# Arduino_clone.net
KiCad netlist of a schematic drawn in EAGLE
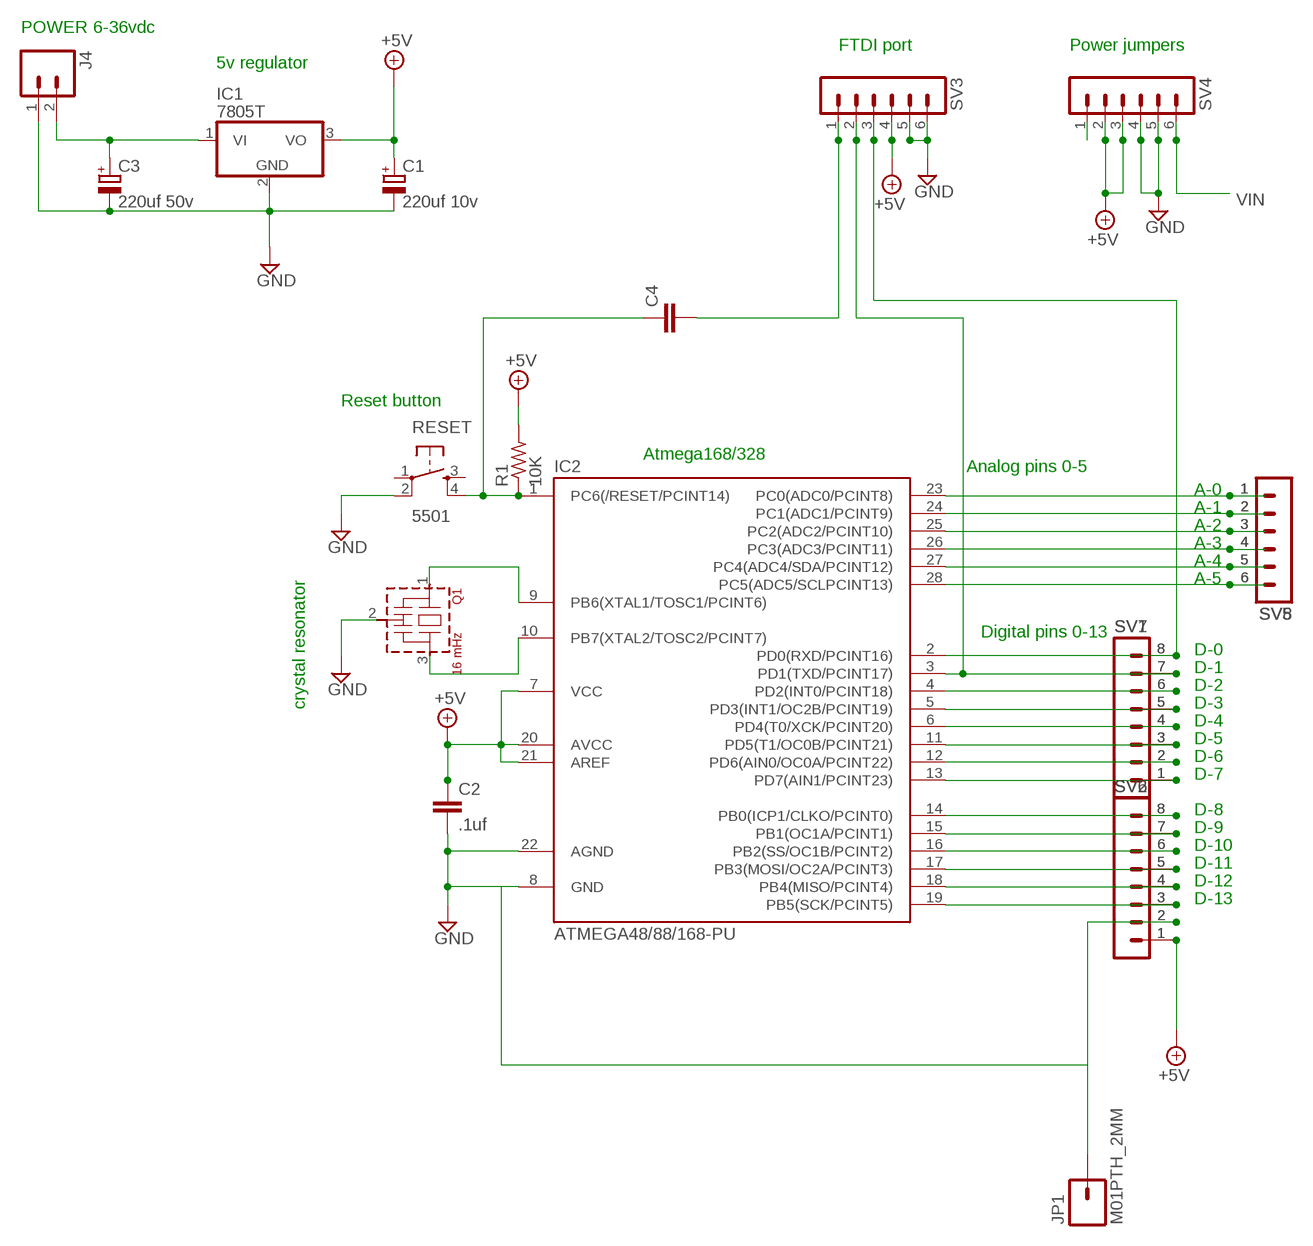
[diagram p0: schematic, sheet 1]

(export (version "E")
  (design (tool "Eeschema 10.0.6"))
  (components
    (comp (ref "C1")
      (value "220uf 10v")
      (footprint "eagle-import:E2,5-6")
      (libsource (lib "eagle-import") (part "CPOL-EUE2.5-6"))
    )
    (comp (ref "C2")
      (value ".1uf")
      (footprint "eagle-import:C050-024X044")
      (libsource (lib "eagle-import") (part "C-EU050-024X044"))
    )
    (comp (ref "C3")
      (value "220uf 50v")
      (footprint "eagle-import:E2,5-6")
      (libsource (lib "eagle-import") (part "CPOL-EUE2.5-6"))
    )
    (comp (ref "C4")
      (value "C-EU075-032X103")
      (footprint "eagle-import:C075-032X103")
      (libsource (lib "eagle-import") (part "C-EU075-032X103"))
    )
    (comp (ref "IC1")
      (value "7805T")
      (footprint "eagle-import:TO220H")
      (libsource (lib "eagle-import") (part "78T05"))
    )
    (comp (ref "IC2")
      (value "ATMEGA48/88/168-PU")
      (footprint "eagle-import:DIL28-3")
      (libsource (lib "eagle-import") (part "ATMEGA48/88/168-PU"))
    )
    (comp (ref "J4")
      (value "M02LOCK")
      (footprint "eagle-import:1X02_LOCK")
      (libsource (lib "eagle-import") (part "M02LOCK"))
    )
    (comp (ref "JP1")
      (value "M01PTH_2MM")
      (footprint "eagle-import:1X01_2MM")
      (libsource (lib "eagle-import") (part "M01PTH_2MM"))
    )
    (comp (ref "Q1")
      (value "16 mHz")
      (footprint "eagle-import:CSTLS_X")
      (libsource (lib "eagle-import") (part "CSTLS_X"))
    )
    (comp (ref "R1")
      (value "10K")
      (footprint "eagle-import:0204_5")
      (libsource (lib "eagle-import") (part "R-US_0204/5"))
    )
    (comp (ref "RESET")
      (value "5501")
      (footprint "eagle-import:TACTILE-PTH")
      (libsource (lib "eagle-import") (part "TAC_SWITCHPTH"))
    )
    (comp (ref "SV1")
      (value "MA08-1")
      (footprint "eagle-import:MA08-1")
      (libsource (lib "eagle-import") (part "MA08-1"))
    )
    (comp (ref "SV2")
      (value "MA08-1")
      (footprint "eagle-import:MA08-1")
      (libsource (lib "eagle-import") (part "MA08-1"))
    )
    (comp (ref "SV3")
      (value "MA06-1")
      (footprint "eagle-import:MA06-1")
      (libsource (lib "eagle-import") (part "MA06-1"))
    )
    (comp (ref "SV4")
      (value "MA06-1")
      (footprint "eagle-import:MA06-1")
      (libsource (lib "eagle-import") (part "MA06-1"))
    )
    (comp (ref "SV5")
      (value "MA06-1")
      (footprint "eagle-import:MA06-1")
      (libsource (lib "eagle-import") (part "MA06-1"))
    )
    (comp (ref "SV6")
      (value "MA08-1")
      (footprint "eagle-import:MA08-1")
      (libsource (lib "eagle-import") (part "MA08-1"))
    )
    (comp (ref "SV7")
      (value "MA08-1")
      (footprint "eagle-import:MA08-1")
      (libsource (lib "eagle-import") (part "MA08-1"))
    )
    (comp (ref "SV8")
      (value "MA06-1")
      (footprint "eagle-import:MA06-1")
      (libsource (lib "eagle-import") (part "MA06-1"))
    )
  )
  (nets
    (net (code "1") (name "+5V") (class "Default")
      (node (ref "C1") (pin "+") (pinfunction "+_+") (pintype "passive"))
      (node (ref "C2") (pin "1") (pinfunction "1_1") (pintype "passive"))
      (node (ref "IC1") (pin "3") (pinfunction "VO_3") (pintype "passive"))
      (node (ref "IC2") (pin "20") (pinfunction "AVCC_20") (pintype "passive"))
      (node (ref "IC2") (pin "21") (pinfunction "AREF_21") (pintype "passive"))
      (node (ref "IC2") (pin "7") (pinfunction "VCC_7") (pintype "power_in"))
      (node (ref "R1") (pin "2") (pinfunction "2_2") (pintype "passive"))
      (node (ref "SV2") (pin "1") (pinfunction "1_1") (pintype "passive"))
      (node (ref "SV3") (pin "4") (pinfunction "4_4") (pintype "passive"))
      (node (ref "SV4") (pin "2") (pinfunction "2_2") (pintype "passive"))
      (node (ref "SV4") (pin "3") (pinfunction "3_3") (pintype "passive"))
      (node (ref "SV6") (pin "1") (pinfunction "1_1") (pintype "passive"))
    )
    (net (code "2") (name "/VIN") (class "Default")
      (node (ref "C3") (pin "+") (pinfunction "+_+") (pintype "passive"))
      (node (ref "IC1") (pin "1") (pinfunction "VI_1") (pintype "input"))
      (node (ref "J4") (pin "2") (pinfunction "2_2") (pintype "passive"))
      (node (ref "SV4") (pin "6") (pinfunction "6_6") (pintype "passive"))
    )
    (net (code "3") (name "GND") (class "Default")
      (node (ref "C1") (pin "-") (pinfunction "-_-") (pintype "passive"))
      (node (ref "C2") (pin "2") (pinfunction "2_2") (pintype "passive"))
      (node (ref "C3") (pin "-") (pinfunction "-_-") (pintype "passive"))
      (node (ref "IC1") (pin "2") (pinfunction "GND_2") (pintype "passive"))
      (node (ref "IC2") (pin "22") (pinfunction "AGND_22") (pintype "power_in"))
      (node (ref "IC2") (pin "8") (pinfunction "GND_8") (pintype "power_in"))
      (node (ref "J4") (pin "1") (pinfunction "1_1") (pintype "passive"))
      (node (ref "JP1") (pin "1") (pinfunction "1_1") (pintype "passive"))
      (node (ref "Q1") (pin "2") (pinfunction "VSS_2") (pintype "power_in"))
      (node (ref "RESET") (pin "2") (pinfunction "2_2") (pintype "passive"))
      (node (ref "SV2") (pin "2") (pinfunction "2_2") (pintype "passive"))
      (node (ref "SV3") (pin "5") (pinfunction "5_5") (pintype "passive"))
      (node (ref "SV3") (pin "6") (pinfunction "6_6") (pintype "passive"))
      (node (ref "SV4") (pin "4") (pinfunction "4_4") (pintype "passive"))
      (node (ref "SV4") (pin "5") (pinfunction "5_5") (pintype "passive"))
      (node (ref "SV6") (pin "2") (pinfunction "2_2") (pintype "passive"))
    )
    (net (code "4") (name "Net-(C4-Pad2)") (class "Default")
      (node (ref "C4") (pin "2") (pinfunction "2_2") (pintype "passive"))
      (node (ref "SV3") (pin "1") (pinfunction "1_1") (pintype "passive"))
    )
    (net (code "5") (name "Net-(IC2-PB0(ICP1{slash}CLKO{slash}PCINT0))") (class "Default")
      (node (ref "IC2") (pin "14") (pinfunction "PB0(ICP1/CLKO/PCINT0)_14") (pintype "bidirectional"))
      (node (ref "SV2") (pin "8") (pinfunction "8_8") (pintype "passive"))
      (node (ref "SV6") (pin "8") (pinfunction "8_8") (pintype "passive"))
    )
    (net (code "6") (name "Net-(IC2-PB1(OC1A{slash}PCINT1))") (class "Default")
      (node (ref "IC2") (pin "15") (pinfunction "PB1(OC1A/PCINT1)_15") (pintype "bidirectional"))
      (node (ref "SV2") (pin "7") (pinfunction "7_7") (pintype "passive"))
      (node (ref "SV6") (pin "7") (pinfunction "7_7") (pintype "passive"))
    )
    (net (code "7") (name "Net-(IC2-PB2(SS{slash}OC1B{slash}PCINT2))") (class "Default")
      (node (ref "IC2") (pin "16") (pinfunction "PB2(SS/OC1B/PCINT2)_16") (pintype "bidirectional"))
      (node (ref "SV2") (pin "6") (pinfunction "6_6") (pintype "passive"))
      (node (ref "SV6") (pin "6") (pinfunction "6_6") (pintype "passive"))
    )
    (net (code "8") (name "Net-(IC2-PB3(MOSI{slash}OC2A{slash}PCINT3))") (class "Default")
      (node (ref "IC2") (pin "17") (pinfunction "PB3(MOSI/OC2A/PCINT3)_17") (pintype "bidirectional"))
      (node (ref "SV2") (pin "5") (pinfunction "5_5") (pintype "passive"))
      (node (ref "SV6") (pin "5") (pinfunction "5_5") (pintype "passive"))
    )
    (net (code "9") (name "Net-(IC2-PB4(MISO{slash}PCINT4))") (class "Default")
      (node (ref "IC2") (pin "18") (pinfunction "PB4(MISO/PCINT4)_18") (pintype "bidirectional"))
      (node (ref "SV2") (pin "4") (pinfunction "4_4") (pintype "passive"))
      (node (ref "SV6") (pin "4") (pinfunction "4_4") (pintype "passive"))
    )
    (net (code "10") (name "Net-(IC2-PB5(SCK{slash}PCINT5))") (class "Default")
      (node (ref "IC2") (pin "19") (pinfunction "PB5(SCK/PCINT5)_19") (pintype "bidirectional"))
      (node (ref "SV2") (pin "3") (pinfunction "3_3") (pintype "passive"))
      (node (ref "SV6") (pin "3") (pinfunction "3_3") (pintype "passive"))
    )
    (net (code "11") (name "Net-(IC2-PB6(XTAL1{slash}TOSC1{slash}PCINT6))") (class "Default")
      (node (ref "IC2") (pin "9") (pinfunction "PB6(XTAL1/TOSC1/PCINT6)_9") (pintype "bidirectional"))
      (node (ref "Q1") (pin "1") (pinfunction "1_1") (pintype "output"))
    )
    (net (code "12") (name "Net-(IC2-PB7(XTAL2{slash}TOSC2{slash}PCINT7))") (class "Default")
      (node (ref "IC2") (pin "10") (pinfunction "PB7(XTAL2/TOSC2/PCINT7)_10") (pintype "bidirectional"))
      (node (ref "Q1") (pin "3") (pinfunction "3_3") (pintype "input"))
    )
    (net (code "13") (name "Net-(IC2-PC0(ADC0{slash}PCINT8))") (class "Default")
      (node (ref "IC2") (pin "23") (pinfunction "PC0(ADC0/PCINT8)_23") (pintype "bidirectional"))
      (node (ref "SV5") (pin "1") (pinfunction "1_1") (pintype "passive"))
      (node (ref "SV8") (pin "1") (pinfunction "1_1") (pintype "passive"))
    )
    (net (code "14") (name "Net-(IC2-PC1(ADC1{slash}PCINT9))") (class "Default")
      (node (ref "IC2") (pin "24") (pinfunction "PC1(ADC1/PCINT9)_24") (pintype "bidirectional"))
      (node (ref "SV5") (pin "2") (pinfunction "2_2") (pintype "passive"))
      (node (ref "SV8") (pin "2") (pinfunction "2_2") (pintype "passive"))
    )
    (net (code "15") (name "Net-(IC2-PC2(ADC2{slash}PCINT10))") (class "Default")
      (node (ref "IC2") (pin "25") (pinfunction "PC2(ADC2/PCINT10)_25") (pintype "bidirectional"))
      (node (ref "SV5") (pin "3") (pinfunction "3_3") (pintype "passive"))
      (node (ref "SV8") (pin "3") (pinfunction "3_3") (pintype "passive"))
    )
    (net (code "16") (name "Net-(IC2-PC3(ADC3{slash}PCINT11))") (class "Default")
      (node (ref "IC2") (pin "26") (pinfunction "PC3(ADC3/PCINT11)_26") (pintype "bidirectional"))
      (node (ref "SV5") (pin "4") (pinfunction "4_4") (pintype "passive"))
      (node (ref "SV8") (pin "4") (pinfunction "4_4") (pintype "passive"))
    )
    (net (code "17") (name "Net-(IC2-PC4(ADC4{slash}SDA{slash}PCINT12))") (class "Default")
      (node (ref "IC2") (pin "27") (pinfunction "PC4(ADC4/SDA/PCINT12)_27") (pintype "bidirectional"))
      (node (ref "SV5") (pin "5") (pinfunction "5_5") (pintype "passive"))
      (node (ref "SV8") (pin "5") (pinfunction "5_5") (pintype "passive"))
    )
    (net (code "18") (name "Net-(IC2-PC5(ADC5{slash}SCLPCINT13))") (class "Default")
      (node (ref "IC2") (pin "28") (pinfunction "PC5(ADC5/SCLPCINT13)_28") (pintype "bidirectional"))
      (node (ref "SV5") (pin "6") (pinfunction "6_6") (pintype "passive"))
      (node (ref "SV8") (pin "6") (pinfunction "6_6") (pintype "passive"))
    )
    (net (code "19") (name "Net-(IC2-PC6({slash}RESET{slash}PCINT14))") (class "Default")
      (node (ref "C4") (pin "1") (pinfunction "1_1") (pintype "passive"))
      (node (ref "IC2") (pin "1") (pinfunction "PC6(/RESET/PCINT14)_1") (pintype "bidirectional"))
      (node (ref "R1") (pin "1") (pinfunction "1_1") (pintype "passive"))
      (node (ref "RESET") (pin "4") (pinfunction "4_4") (pintype "passive"))
    )
    (net (code "20") (name "Net-(IC2-PD0(RXD{slash}PCINT16))") (class "Default")
      (node (ref "IC2") (pin "2") (pinfunction "PD0(RXD/PCINT16)_2") (pintype "bidirectional"))
      (node (ref "SV1") (pin "8") (pinfunction "8_8") (pintype "passive"))
      (node (ref "SV3") (pin "3") (pinfunction "3_3") (pintype "passive"))
      (node (ref "SV7") (pin "8") (pinfunction "8_8") (pintype "passive"))
    )
    (net (code "21") (name "Net-(IC2-PD1(TXD{slash}PCINT17))") (class "Default")
      (node (ref "IC2") (pin "3") (pinfunction "PD1(TXD/PCINT17)_3") (pintype "bidirectional"))
      (node (ref "SV1") (pin "7") (pinfunction "7_7") (pintype "passive"))
      (node (ref "SV3") (pin "2") (pinfunction "2_2") (pintype "passive"))
      (node (ref "SV7") (pin "7") (pinfunction "7_7") (pintype "passive"))
    )
    (net (code "22") (name "Net-(IC2-PD2(INT0{slash}PCINT18))") (class "Default")
      (node (ref "IC2") (pin "4") (pinfunction "PD2(INT0/PCINT18)_4") (pintype "bidirectional"))
      (node (ref "SV1") (pin "6") (pinfunction "6_6") (pintype "passive"))
      (node (ref "SV7") (pin "6") (pinfunction "6_6") (pintype "passive"))
    )
    (net (code "23") (name "Net-(IC2-PD3(INT1{slash}OC2B{slash}PCINT19))") (class "Default")
      (node (ref "IC2") (pin "5") (pinfunction "PD3(INT1/OC2B/PCINT19)_5") (pintype "bidirectional"))
      (node (ref "SV1") (pin "5") (pinfunction "5_5") (pintype "passive"))
      (node (ref "SV7") (pin "5") (pinfunction "5_5") (pintype "passive"))
    )
    (net (code "24") (name "Net-(IC2-PD4(T0{slash}XCK{slash}PCINT20))") (class "Default")
      (node (ref "IC2") (pin "6") (pinfunction "PD4(T0/XCK/PCINT20)_6") (pintype "bidirectional"))
      (node (ref "SV1") (pin "4") (pinfunction "4_4") (pintype "passive"))
      (node (ref "SV7") (pin "4") (pinfunction "4_4") (pintype "passive"))
    )
    (net (code "25") (name "Net-(IC2-PD5(T1{slash}OC0B{slash}PCINT21))") (class "Default")
      (node (ref "IC2") (pin "11") (pinfunction "PD5(T1/OC0B/PCINT21)_11") (pintype "bidirectional"))
      (node (ref "SV1") (pin "3") (pinfunction "3_3") (pintype "passive"))
      (node (ref "SV7") (pin "3") (pinfunction "3_3") (pintype "passive"))
    )
    (net (code "26") (name "Net-(IC2-PD6(AIN0{slash}OC0A{slash}PCINT22))") (class "Default")
      (node (ref "IC2") (pin "12") (pinfunction "PD6(AIN0/OC0A/PCINT22)_12") (pintype "bidirectional"))
      (node (ref "SV1") (pin "2") (pinfunction "2_2") (pintype "passive"))
      (node (ref "SV7") (pin "2") (pinfunction "2_2") (pintype "passive"))
    )
    (net (code "27") (name "Net-(IC2-PD7(AIN1{slash}PCINT23))") (class "Default")
      (node (ref "IC2") (pin "13") (pinfunction "PD7(AIN1/PCINT23)_13") (pintype "bidirectional"))
      (node (ref "SV1") (pin "1") (pinfunction "1_1") (pintype "passive"))
      (node (ref "SV7") (pin "1") (pinfunction "1_1") (pintype "passive"))
    )
    (net (code "28") (name "unconnected-(RESET-Pad1)") (class "Default")
      (node (ref "RESET") (pin "1") (pinfunction "1_1") (pintype "passive"))
    )
    (net (code "29") (name "unconnected-(RESET-Pad3)") (class "Default")
      (node (ref "RESET") (pin "3") (pinfunction "3_3") (pintype "passive"))
    )
    (net (code "30") (name "unconnected-(SV4-Pad1)") (class "Default")
      (node (ref "SV4") (pin "1") (pinfunction "1_1") (pintype "passive"))
    )
  )
)
